# LowTemp_singleboard.net
KiCad netlist of a schematic drawn in EAGLE
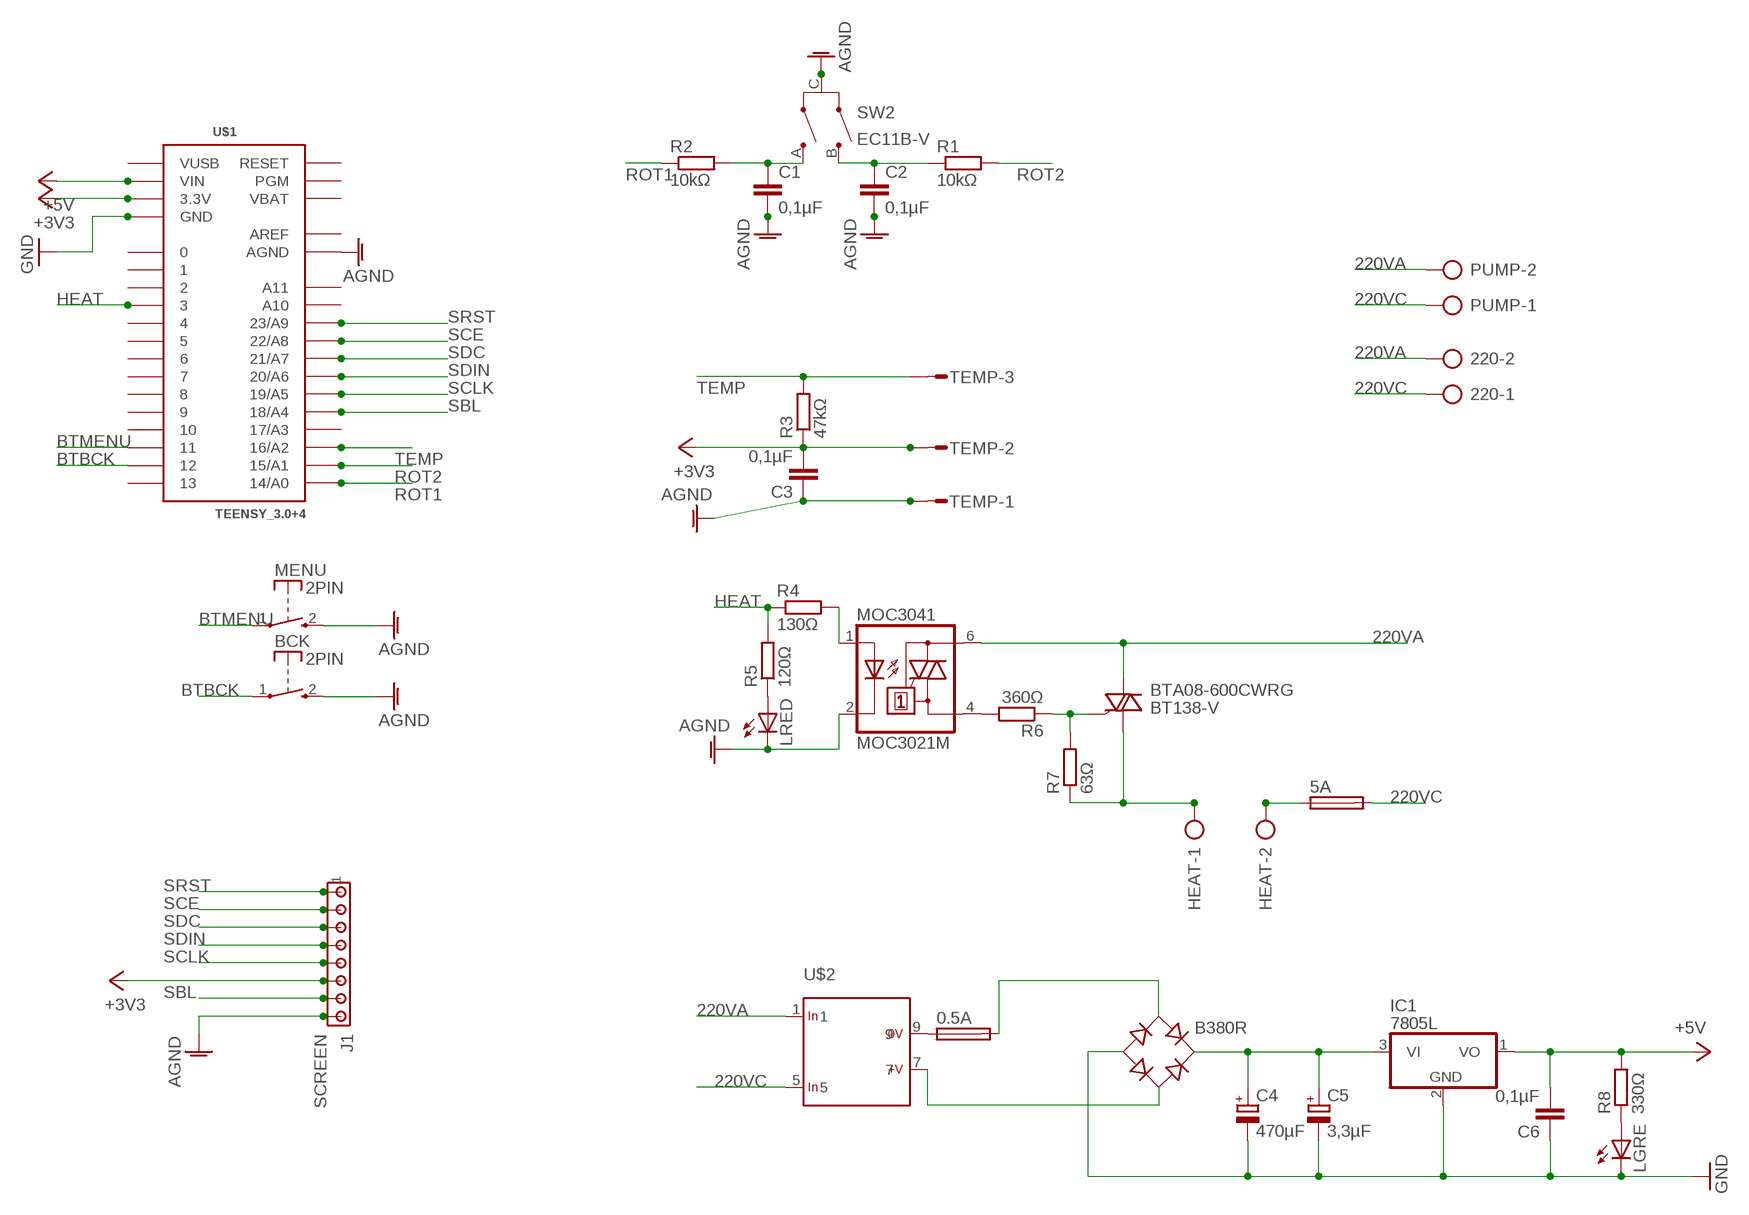
[diagram p0: schematic, sheet 1]

(export (version "E")
  (design (tool "Eeschema 10.0.6"))
  (components
    (comp (ref "0.5A")
      (value "SH22,5A")
      (footprint "eagle-import:SH22,5A")
      (fields (field (name "MPN") "0031.7701.11"))
      (libsource (lib "eagle-import") (part "SH22,5A"))
    )
    (comp (ref "5A")
      (value "SH22,5A")
      (footprint "eagle-import:SH22,5A")
      (fields (field (name "MPN") "0031.7701.11"))
      (libsource (lib "eagle-import") (part "SH22,5A"))
    )
    (comp (ref "220")
      (value "AK500/2-H")
      (footprint "eagle-import:AK500_2-H")
      (libsource (lib "eagle-import") (part "AK500/2-H"))
    )
    (comp (ref "B380R")
      (value "RB1A")
      (footprint "eagle-import:RB1A")
      (libsource (lib "eagle-import") (part "RB1A"))
    )
    (comp (ref "BCK")
      (value "2PIN")
      (footprint "eagle-import:2PIN")
      (libsource (lib "eagle-import") (part "2PIN"))
    )
    (comp (ref "BTA08-600CWRG")
      (value "BT138-V")
      (footprint "eagle-import:TO220BV")
      (libsource (lib "eagle-import") (part "BT138-V"))
    )
    (comp (ref "C1")
      (value "0,1µF")
      (footprint "eagle-import:C050-025X075")
      (libsource (lib "eagle-import") (part "C-EU050-025X075"))
    )
    (comp (ref "C2")
      (value "0,1µF")
      (footprint "eagle-import:C050-025X075")
      (libsource (lib "eagle-import") (part "C-EU050-025X075"))
    )
    (comp (ref "C3")
      (value "0,1µF")
      (footprint "eagle-import:C050-025X075")
      (libsource (lib "eagle-import") (part "C-EU050-025X075"))
    )
    (comp (ref "C4")
      (value "470µF")
      (footprint "eagle-import:E5-8,5")
      (libsource (lib "eagle-import") (part "CPOL-EUE5-8.5"))
    )
    (comp (ref "C5")
      (value "3,3µF")
      (footprint "eagle-import:TT2D4")
      (libsource (lib "eagle-import") (part "CPOL-EUTT2D4"))
    )
    (comp (ref "C6")
      (value "0,1µF")
      (footprint "eagle-import:C050-025X075")
      (libsource (lib "eagle-import") (part "C-EU050-025X075"))
    )
    (comp (ref "HEAT")
      (value "AK500/2-H")
      (footprint "eagle-import:AK500_2-H")
      (libsource (lib "eagle-import") (part "AK500/2-H"))
    )
    (comp (ref "IC1")
      (value "7805L")
      (footprint "eagle-import:TO92")
      (libsource (lib "eagle-import") (part "78L05"))
    )
    (comp (ref "J1")
      (value "SCREEN")
      (footprint "eagle-import:10X08MTA")
      (libsource (lib "eagle-import") (part "MTA08-100"))
    )
    (comp (ref "LGRE")
      (value "LED5MM")
      (footprint "eagle-import:LED5MM")
      (libsource (lib "eagle-import") (part "LED5MM"))
    )
    (comp (ref "LRED")
      (value "LED5MM")
      (footprint "eagle-import:LED5MM")
      (libsource (lib "eagle-import") (part "LED5MM"))
    )
    (comp (ref "MENU")
      (value "2PIN")
      (footprint "eagle-import:2PIN")
      (libsource (lib "eagle-import") (part "2PIN"))
    )
    (comp (ref "MOC3041")
      (value "MOC3021M")
      (footprint "eagle-import:DIL06")
      (fields (field (name "MF") "FAIRCHILD SEMICONDUCTOR") (field (name "MPN") "MOC3021-M"))
      (libsource (lib "eagle-import") (part "MOC30M21"))
    )
    (comp (ref "PUMP")
      (value "AK500/2-H")
      (footprint "eagle-import:AK500_2-H")
      (libsource (lib "eagle-import") (part "AK500/2-H"))
    )
    (comp (ref "R1")
      (value "10kΩ")
      (footprint "eagle-import:0207_7")
      (libsource (lib "eagle-import") (part "R-EU_0207/7"))
    )
    (comp (ref "R2")
      (value "10kΩ")
      (footprint "eagle-import:0207_7")
      (libsource (lib "eagle-import") (part "R-EU_0207/7"))
    )
    (comp (ref "R3")
      (value "47kΩ")
      (footprint "eagle-import:0207_7")
      (libsource (lib "eagle-import") (part "R-EU_0207/7"))
    )
    (comp (ref "R4")
      (value "130Ω")
      (footprint "eagle-import:0207_7")
      (libsource (lib "eagle-import") (part "R-EU_0207/7"))
    )
    (comp (ref "R5")
      (value "120Ω")
      (footprint "eagle-import:0207_7")
      (libsource (lib "eagle-import") (part "R-EU_0207/7"))
    )
    (comp (ref "R6")
      (value "360Ω")
      (footprint "eagle-import:0207_7")
      (libsource (lib "eagle-import") (part "R-EU_0207/7"))
    )
    (comp (ref "R7")
      (value "63Ω")
      (footprint "eagle-import:0207_7")
      (libsource (lib "eagle-import") (part "R-EU_0207/7"))
    )
    (comp (ref "R8")
      (value "330Ω")
      (footprint "eagle-import:0207_7")
      (libsource (lib "eagle-import") (part "R-EU_0207/7"))
    )
    (comp (ref "SW2")
      (value "EC11B-V")
      (footprint "eagle-import:EC11B-V")
      (libsource (lib "eagle-import") (part "EC11B-V"))
    )
    (comp (ref "TEMP")
      (value "S03P")
      (footprint "eagle-import:S03P")
      (libsource (lib "eagle-import") (part "S03P"))
    )
    (comp (ref "U$1")
      (value "TEENSY_3.0+4")
      (footprint "eagle-import:TEENSY_3.0+4")
      (libsource (lib "eagle-import") (part "TEENSY_3.0+4"))
    )
    (comp (ref "U$2")
      (value "SINGLE")
      (footprint "eagle-import:1")
      (libsource (lib "eagle-import") (part "SINGLE"))
    )
  )
  (nets
    (net (code "1") (name "+3V3") (class "Default")
      (node (ref "C3") (pin "2") (pinfunction "2_2") (pintype "passive"))
      (node (ref "J1") (pin "6") (pinfunction "6_6") (pintype "passive"))
      (node (ref "R3") (pin "1") (pinfunction "1_1") (pintype "passive"))
      (node (ref "TEMP") (pin "2") (pinfunction "S_2") (pintype "passive"))
      (node (ref "U$1") (pin "3.3V") (pinfunction "3.3V_3.3V") (pintype "power_in"))
      (node (ref "U$1") (pin "3.3V1") (pinfunction "3.3V_3.3V1") (pintype "power_in"))
    )
    (net (code "2") (name "+5V") (class "Default")
      (node (ref "C6") (pin "2") (pinfunction "2_2") (pintype "passive"))
      (node (ref "IC1") (pin "1") (pinfunction "VO_1") (pintype "passive"))
      (node (ref "R8") (pin "2") (pinfunction "2_2") (pintype "passive"))
      (node (ref "U$1") (pin "VIN") (pinfunction "VIN_VIN") (pintype "power_in"))
    )
    (net (code "3") (name "/220VA") (class "Default")
      (node (ref "220") (pin "2") (pinfunction "KL_2") (pintype "passive"))
      (node (ref "BTA08-600CWRG") (pin "T2") (pinfunction "A2_T2") (pintype "passive"))
      (node (ref "MOC3041") (pin "6") (pinfunction "A2_6") (pintype "passive"))
      (node (ref "PUMP") (pin "2") (pinfunction "KL_2") (pintype "passive"))
      (node (ref "U$2") (pin "1") (pinfunction "1_1") (pintype "input"))
    )
    (net (code "4") (name "/220VC") (class "Default")
      (node (ref "220") (pin "1") (pinfunction "KL_1") (pintype "passive"))
      (node (ref "5A") (pin "2") (pinfunction "2_2") (pintype "passive"))
      (node (ref "PUMP") (pin "1") (pinfunction "KL_1") (pintype "passive"))
      (node (ref "U$2") (pin "5") (pinfunction "5_5") (pintype "input"))
    )
    (net (code "5") (name "/AREF") (class "Default")
      (node (ref "U$1") (pin "AREF") (pinfunction "AREF_AREF") (pintype "power_in"))
    )
    (net (code "6") (name "/BTBCK") (class "Default")
      (node (ref "BCK") (pin "1") (pinfunction "P_1") (pintype "passive"))
      (node (ref "U$1") (pin "12") (pinfunction "12_12") (pintype "bidirectional"))
    )
    (net (code "7") (name "/BTMENU") (class "Default")
      (node (ref "MENU") (pin "1") (pinfunction "P_1") (pintype "passive"))
      (node (ref "U$1") (pin "11") (pinfunction "11_11") (pintype "bidirectional"))
    )
    (net (code "8") (name "/HEAT") (class "Default")
      (node (ref "R4") (pin "1") (pinfunction "1_1") (pintype "passive"))
      (node (ref "R5") (pin "2") (pinfunction "2_2") (pintype "passive"))
      (node (ref "U$1") (pin "3") (pinfunction "3_3") (pintype "bidirectional"))
    )
    (net (code "9") (name "/ROT1") (class "Default")
      (node (ref "R2") (pin "1") (pinfunction "1_1") (pintype "passive"))
      (node (ref "U$1") (pin "14/A0") (pinfunction "14/A0_14/A0") (pintype "bidirectional"))
    )
    (net (code "10") (name "/ROT2") (class "Default")
      (node (ref "R1") (pin "2") (pinfunction "2_2") (pintype "passive"))
      (node (ref "U$1") (pin "15/A1") (pinfunction "15/A1_15/A1") (pintype "bidirectional"))
    )
    (net (code "11") (name "/SBL") (class "Default")
      (node (ref "J1") (pin "7") (pinfunction "7_7") (pintype "passive"))
      (node (ref "U$1") (pin "18/A4") (pinfunction "18/A4_18/A4") (pintype "bidirectional"))
    )
    (net (code "12") (name "/SCE") (class "Default")
      (node (ref "J1") (pin "2") (pinfunction "2_2") (pintype "passive"))
      (node (ref "U$1") (pin "22/A8") (pinfunction "22/A8_22/A8") (pintype "bidirectional"))
    )
    (net (code "13") (name "/SCLK") (class "Default")
      (node (ref "J1") (pin "5") (pinfunction "5_5") (pintype "passive"))
      (node (ref "U$1") (pin "19/A5") (pinfunction "19/A5_19/A5") (pintype "bidirectional"))
    )
    (net (code "14") (name "/SDC") (class "Default")
      (node (ref "J1") (pin "3") (pinfunction "3_3") (pintype "passive"))
      (node (ref "U$1") (pin "21/A7") (pinfunction "21/A7_21/A7") (pintype "bidirectional"))
    )
    (net (code "15") (name "/SDIN") (class "Default")
      (node (ref "J1") (pin "4") (pinfunction "4_4") (pintype "passive"))
      (node (ref "U$1") (pin "20/A6") (pinfunction "20/A6_20/A6") (pintype "bidirectional"))
    )
    (net (code "16") (name "/SRST") (class "Default")
      (node (ref "J1") (pin "1") (pinfunction "1_1") (pintype "passive"))
      (node (ref "U$1") (pin "23/A9") (pinfunction "23/A9_23/A9") (pintype "bidirectional"))
    )
    (net (code "17") (name "/TEMP") (class "Default")
      (node (ref "R3") (pin "2") (pinfunction "2_2") (pintype "passive"))
      (node (ref "TEMP") (pin "3") (pinfunction "S_3") (pintype "passive"))
      (node (ref "U$1") (pin "16/A2") (pinfunction "16/A2_16/A2") (pintype "bidirectional"))
    )
    (net (code "18") (name "/VBAT") (class "Default")
      (node (ref "U$1") (pin "VBAT") (pinfunction "VBAT_VBAT") (pintype "power_in"))
    )
    (net (code "19") (name "/VUSB") (class "Default")
      (node (ref "U$1") (pin "VUSB") (pinfunction "VUSB_VUSB") (pintype "power_in"))
    )
    (net (code "20") (name "AGND") (class "Default")
      (node (ref "BCK") (pin "2") (pinfunction "S_2") (pintype "passive"))
      (node (ref "C1") (pin "2") (pinfunction "2_2") (pintype "passive"))
      (node (ref "C2") (pin "2") (pinfunction "2_2") (pintype "passive"))
      (node (ref "C3") (pin "1") (pinfunction "1_1") (pintype "passive"))
      (node (ref "J1") (pin "8") (pinfunction "8_8") (pintype "passive"))
      (node (ref "LRED") (pin "K") (pinfunction "C_K") (pintype "passive"))
      (node (ref "MENU") (pin "2") (pinfunction "S_2") (pintype "passive"))
      (node (ref "MOC3041") (pin "2") (pinfunction "C_2") (pintype "passive"))
      (node (ref "SW2") (pin "C") (pinfunction "C_C") (pintype "passive"))
      (node (ref "TEMP") (pin "1") (pinfunction "S_1") (pintype "passive"))
      (node (ref "U$1") (pin "AGND") (pinfunction "AGND_AGND") (pintype "power_in"))
    )
    (net (code "21") (name "GND") (class "Default")
      (node (ref "B380R") (pin "-") (pinfunction "-_-") (pintype "passive"))
      (node (ref "C4") (pin "-") (pinfunction "-_-") (pintype "passive"))
      (node (ref "C5") (pin "-") (pinfunction "-_-") (pintype "passive"))
      (node (ref "C6") (pin "1") (pinfunction "1_1") (pintype "passive"))
      (node (ref "IC1") (pin "2") (pinfunction "GND_2") (pintype "passive"))
      (node (ref "LGRE") (pin "K") (pinfunction "C_K") (pintype "passive"))
      (node (ref "U$1") (pin "GND") (pinfunction "GND_GND") (pintype "power_in"))
      (node (ref "U$1") (pin "GND1") (pinfunction "GND_GND1") (pintype "power_in"))
    )
    (net (code "22") (name "Net-(0.5A-Pad1)") (class "Default")
      (node (ref "0.5A") (pin "1") (pinfunction "1_1") (pintype "passive"))
      (node (ref "U$2") (pin "9") (pinfunction "9_9") (pintype "output"))
    )
    (net (code "23") (name "Net-(0.5A-Pad2)") (class "Default")
      (node (ref "0.5A") (pin "2") (pinfunction "2_2") (pintype "passive"))
      (node (ref "B380R") (pin "AC1") (pinfunction "AC1_AC1") (pintype "passive"))
    )
    (net (code "24") (name "Net-(B380R-PadAC2)") (class "Default")
      (node (ref "B380R") (pin "AC2") (pinfunction "AC2_AC2") (pintype "passive"))
      (node (ref "U$2") (pin "7") (pinfunction "7_7") (pintype "output"))
    )
    (net (code "25") (name "Net-(BTA08-600CWRG-A1)") (class "Default")
      (node (ref "BTA08-600CWRG") (pin "T1") (pinfunction "A1_T1") (pintype "passive"))
      (node (ref "HEAT") (pin "1") (pinfunction "KL_1") (pintype "passive"))
      (node (ref "R7") (pin "1") (pinfunction "1_1") (pintype "passive"))
    )
    (net (code "26") (name "Net-(BTA08-600CWRG-PadG)") (class "Default")
      (node (ref "BTA08-600CWRG") (pin "G") (pinfunction "G_G") (pintype "passive"))
      (node (ref "R6") (pin "1") (pinfunction "1_1") (pintype "passive"))
      (node (ref "R7") (pin "2") (pinfunction "2_2") (pintype "passive"))
    )
    (net (code "27") (name "Net-(C1-Pad1)") (class "Default")
      (node (ref "C1") (pin "1") (pinfunction "1_1") (pintype "passive"))
      (node (ref "R2") (pin "2") (pinfunction "2_2") (pintype "passive"))
      (node (ref "SW2") (pin "A") (pinfunction "A_A") (pintype "passive"))
    )
    (net (code "28") (name "Net-(C2-Pad1)") (class "Default")
      (node (ref "C2") (pin "1") (pinfunction "1_1") (pintype "passive"))
      (node (ref "R1") (pin "1") (pinfunction "1_1") (pintype "passive"))
      (node (ref "SW2") (pin "B") (pinfunction "B_B") (pintype "passive"))
    )
    (net (code "29") (name "Net-(HEATB-KL)") (class "Default")
      (node (ref "5A") (pin "1") (pinfunction "1_1") (pintype "passive"))
      (node (ref "HEAT") (pin "2") (pinfunction "KL_2") (pintype "passive"))
    )
    (net (code "30") (name "Net-(IC1-VI)") (class "Default")
      (node (ref "B380R") (pin "+") (pinfunction "+_+") (pintype "passive"))
      (node (ref "C4") (pin "+") (pinfunction "+_+") (pintype "passive"))
      (node (ref "C5") (pin "+") (pinfunction "+_+") (pintype "passive"))
      (node (ref "IC1") (pin "3") (pinfunction "VI_3") (pintype "input"))
    )
    (net (code "31") (name "Net-(LGRE-PadA)") (class "Default")
      (node (ref "LGRE") (pin "A") (pinfunction "A_A") (pintype "passive"))
      (node (ref "R8") (pin "1") (pinfunction "1_1") (pintype "passive"))
    )
    (net (code "32") (name "Net-(LRED-PadA)") (class "Default")
      (node (ref "LRED") (pin "A") (pinfunction "A_A") (pintype "passive"))
      (node (ref "R5") (pin "1") (pinfunction "1_1") (pintype "passive"))
    )
    (net (code "33") (name "Net-(MOC3041-A)") (class "Default")
      (node (ref "MOC3041") (pin "1") (pinfunction "A_1") (pintype "passive"))
      (node (ref "R4") (pin "2") (pinfunction "2_2") (pintype "passive"))
    )
    (net (code "34") (name "Net-(MOC3041-A1)") (class "Default")
      (node (ref "MOC3041") (pin "4") (pinfunction "A1_4") (pintype "passive"))
      (node (ref "R6") (pin "2") (pinfunction "2_2") (pintype "passive"))
    )
    (net (code "35") (name "unconnected-(U$1-Pad0)") (class "Default")
      (node (ref "U$1") (pin "0") (pinfunction "0_0") (pintype "bidirectional"))
    )
    (net (code "36") (name "unconnected-(U$1-Pad1)") (class "Default")
      (node (ref "U$1") (pin "1") (pinfunction "1_1") (pintype "bidirectional"))
    )
    (net (code "37") (name "unconnected-(U$1-Pad2)") (class "Default")
      (node (ref "U$1") (pin "2") (pinfunction "2_2") (pintype "bidirectional"))
    )
    (net (code "38") (name "unconnected-(U$1-Pad4)") (class "Default")
      (node (ref "U$1") (pin "4") (pinfunction "4_4") (pintype "bidirectional"))
    )
    (net (code "39") (name "unconnected-(U$1-Pad5)") (class "Default")
      (node (ref "U$1") (pin "5") (pinfunction "5_5") (pintype "bidirectional"))
    )
    (net (code "40") (name "unconnected-(U$1-Pad6)") (class "Default")
      (node (ref "U$1") (pin "6") (pinfunction "6_6") (pintype "bidirectional"))
    )
    (net (code "41") (name "unconnected-(U$1-Pad7)") (class "Default")
      (node (ref "U$1") (pin "7") (pinfunction "7_7") (pintype "bidirectional"))
    )
    (net (code "42") (name "unconnected-(U$1-Pad8)") (class "Default")
      (node (ref "U$1") (pin "8") (pinfunction "8_8") (pintype "bidirectional"))
    )
    (net (code "43") (name "unconnected-(U$1-Pad9)") (class "Default")
      (node (ref "U$1") (pin "9") (pinfunction "9_9") (pintype "bidirectional"))
    )
    (net (code "44") (name "unconnected-(U$1-Pad10)") (class "Default")
      (node (ref "U$1") (pin "10") (pinfunction "10_10") (pintype "bidirectional"))
    )
    (net (code "45") (name "unconnected-(U$1-Pad13)") (class "Default")
      (node (ref "U$1") (pin "13") (pinfunction "13_13") (pintype "bidirectional"))
    )
    (net (code "46") (name "unconnected-(U$1-Pad17{slash}A3)") (class "Default")
      (node (ref "U$1") (pin "17/A3") (pinfunction "17/A3_17/A3") (pintype "bidirectional"))
    )
    (net (code "47") (name "unconnected-(U$1-PadA10)") (class "Default")
      (node (ref "U$1") (pin "A10") (pinfunction "A10_A10") (pintype "bidirectional"))
    )
    (net (code "48") (name "unconnected-(U$1-PadA11)") (class "Default")
      (node (ref "U$1") (pin "A11") (pinfunction "A11_A11") (pintype "bidirectional"))
    )
    (net (code "49") (name "unconnected-(U$1-PadPGM)") (class "Default")
      (node (ref "U$1") (pin "PGM") (pinfunction "PGM_PGM") (pintype "bidirectional"))
    )
    (net (code "50") (name "unconnected-(U$1-PadRESET)") (class "Default")
      (node (ref "U$1") (pin "RESET") (pinfunction "RESET_RESET") (pintype "bidirectional"))
    )
  )
)
